# 8Enc.net
KiCad netlist of a schematic drawn in EAGLE
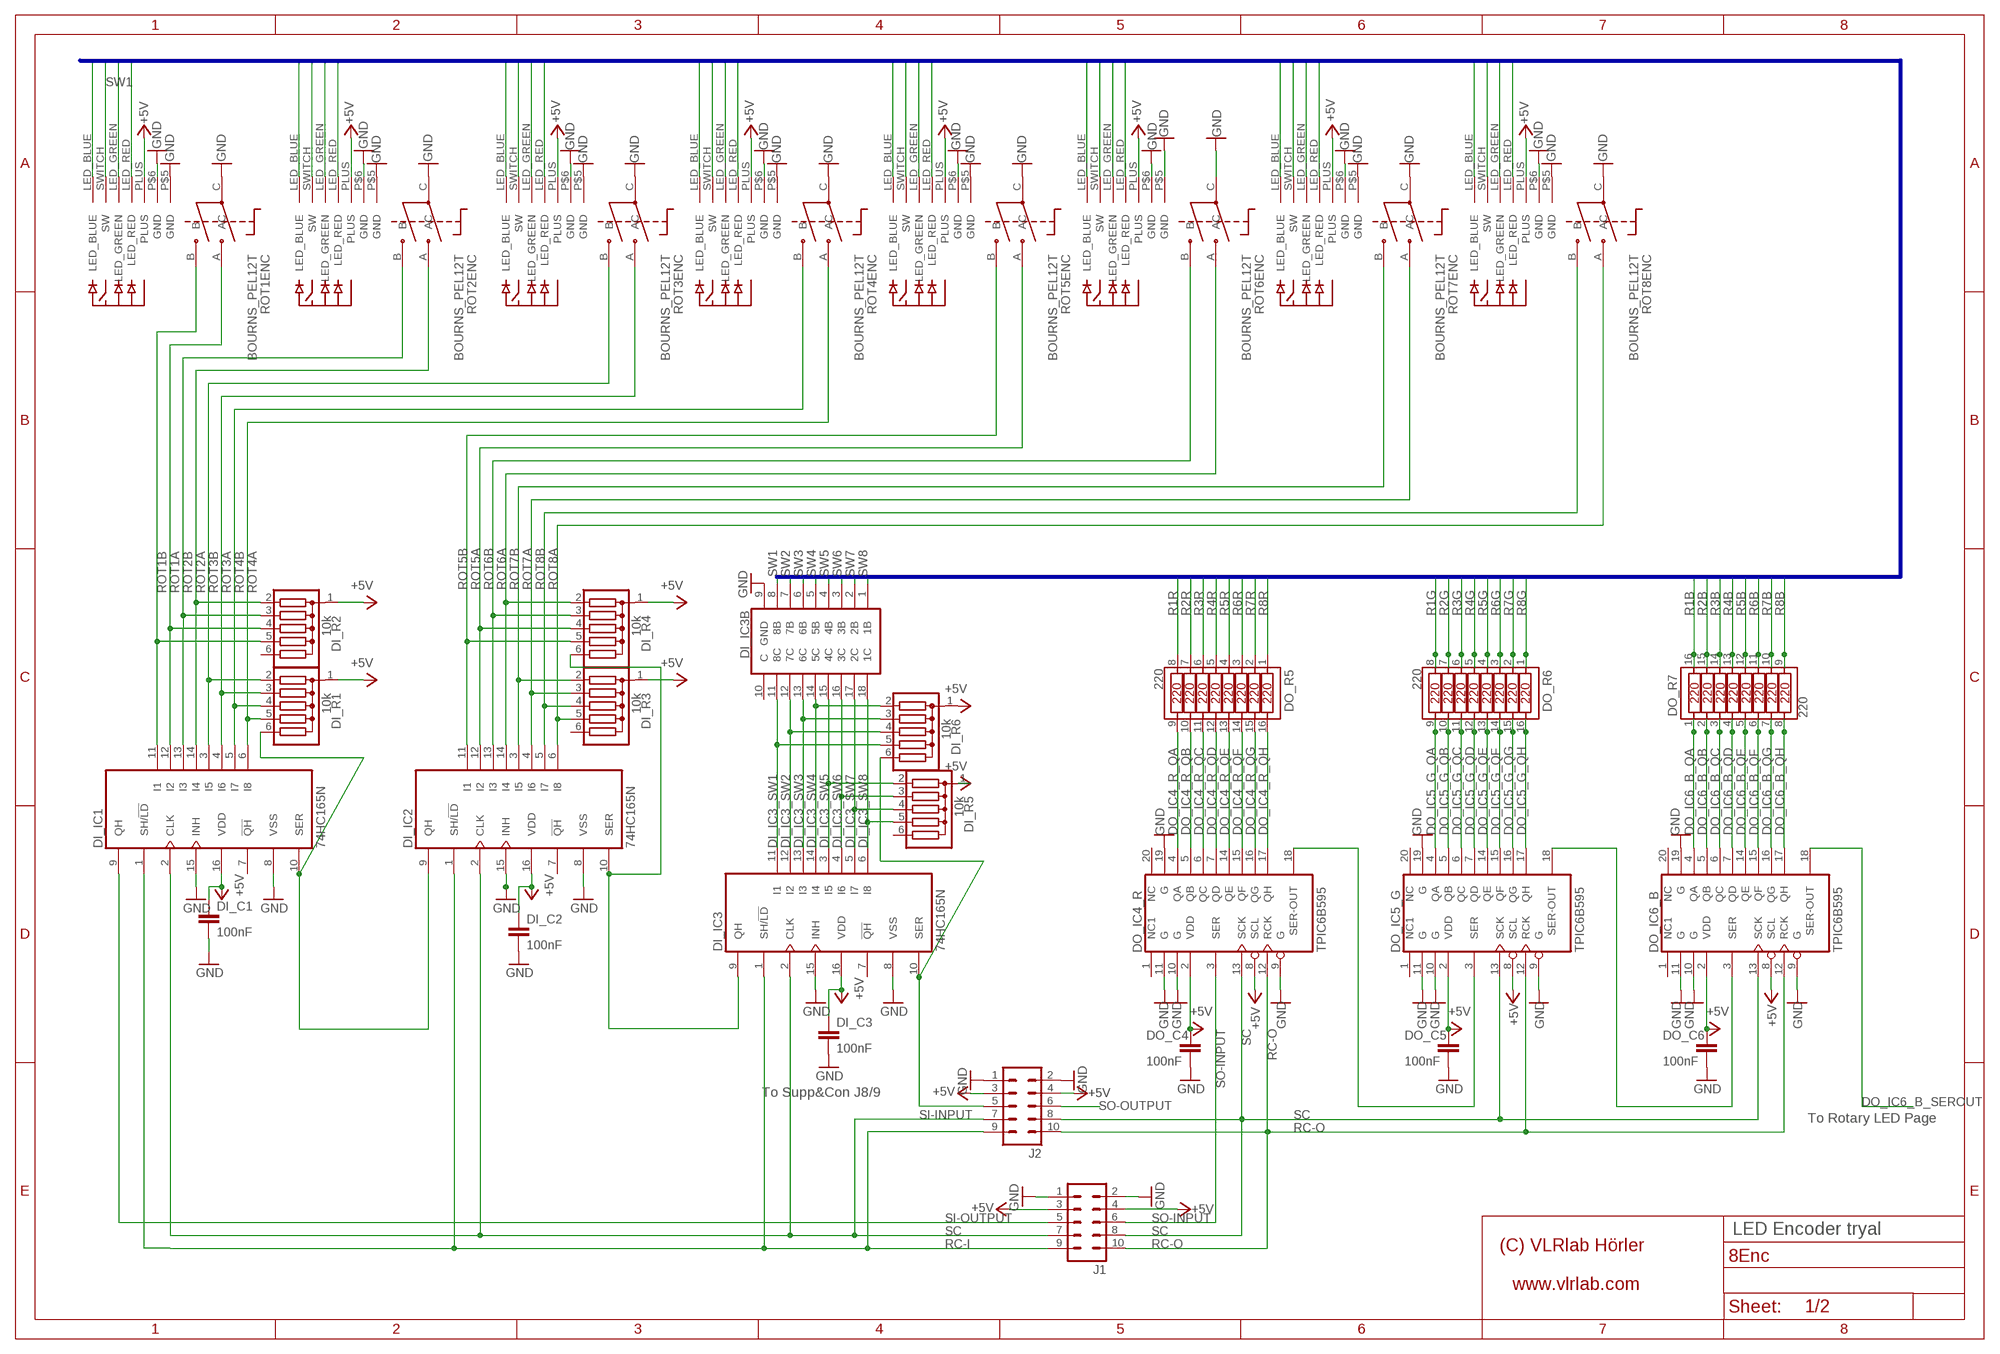
[diagram p0: schematic, sheet 1]
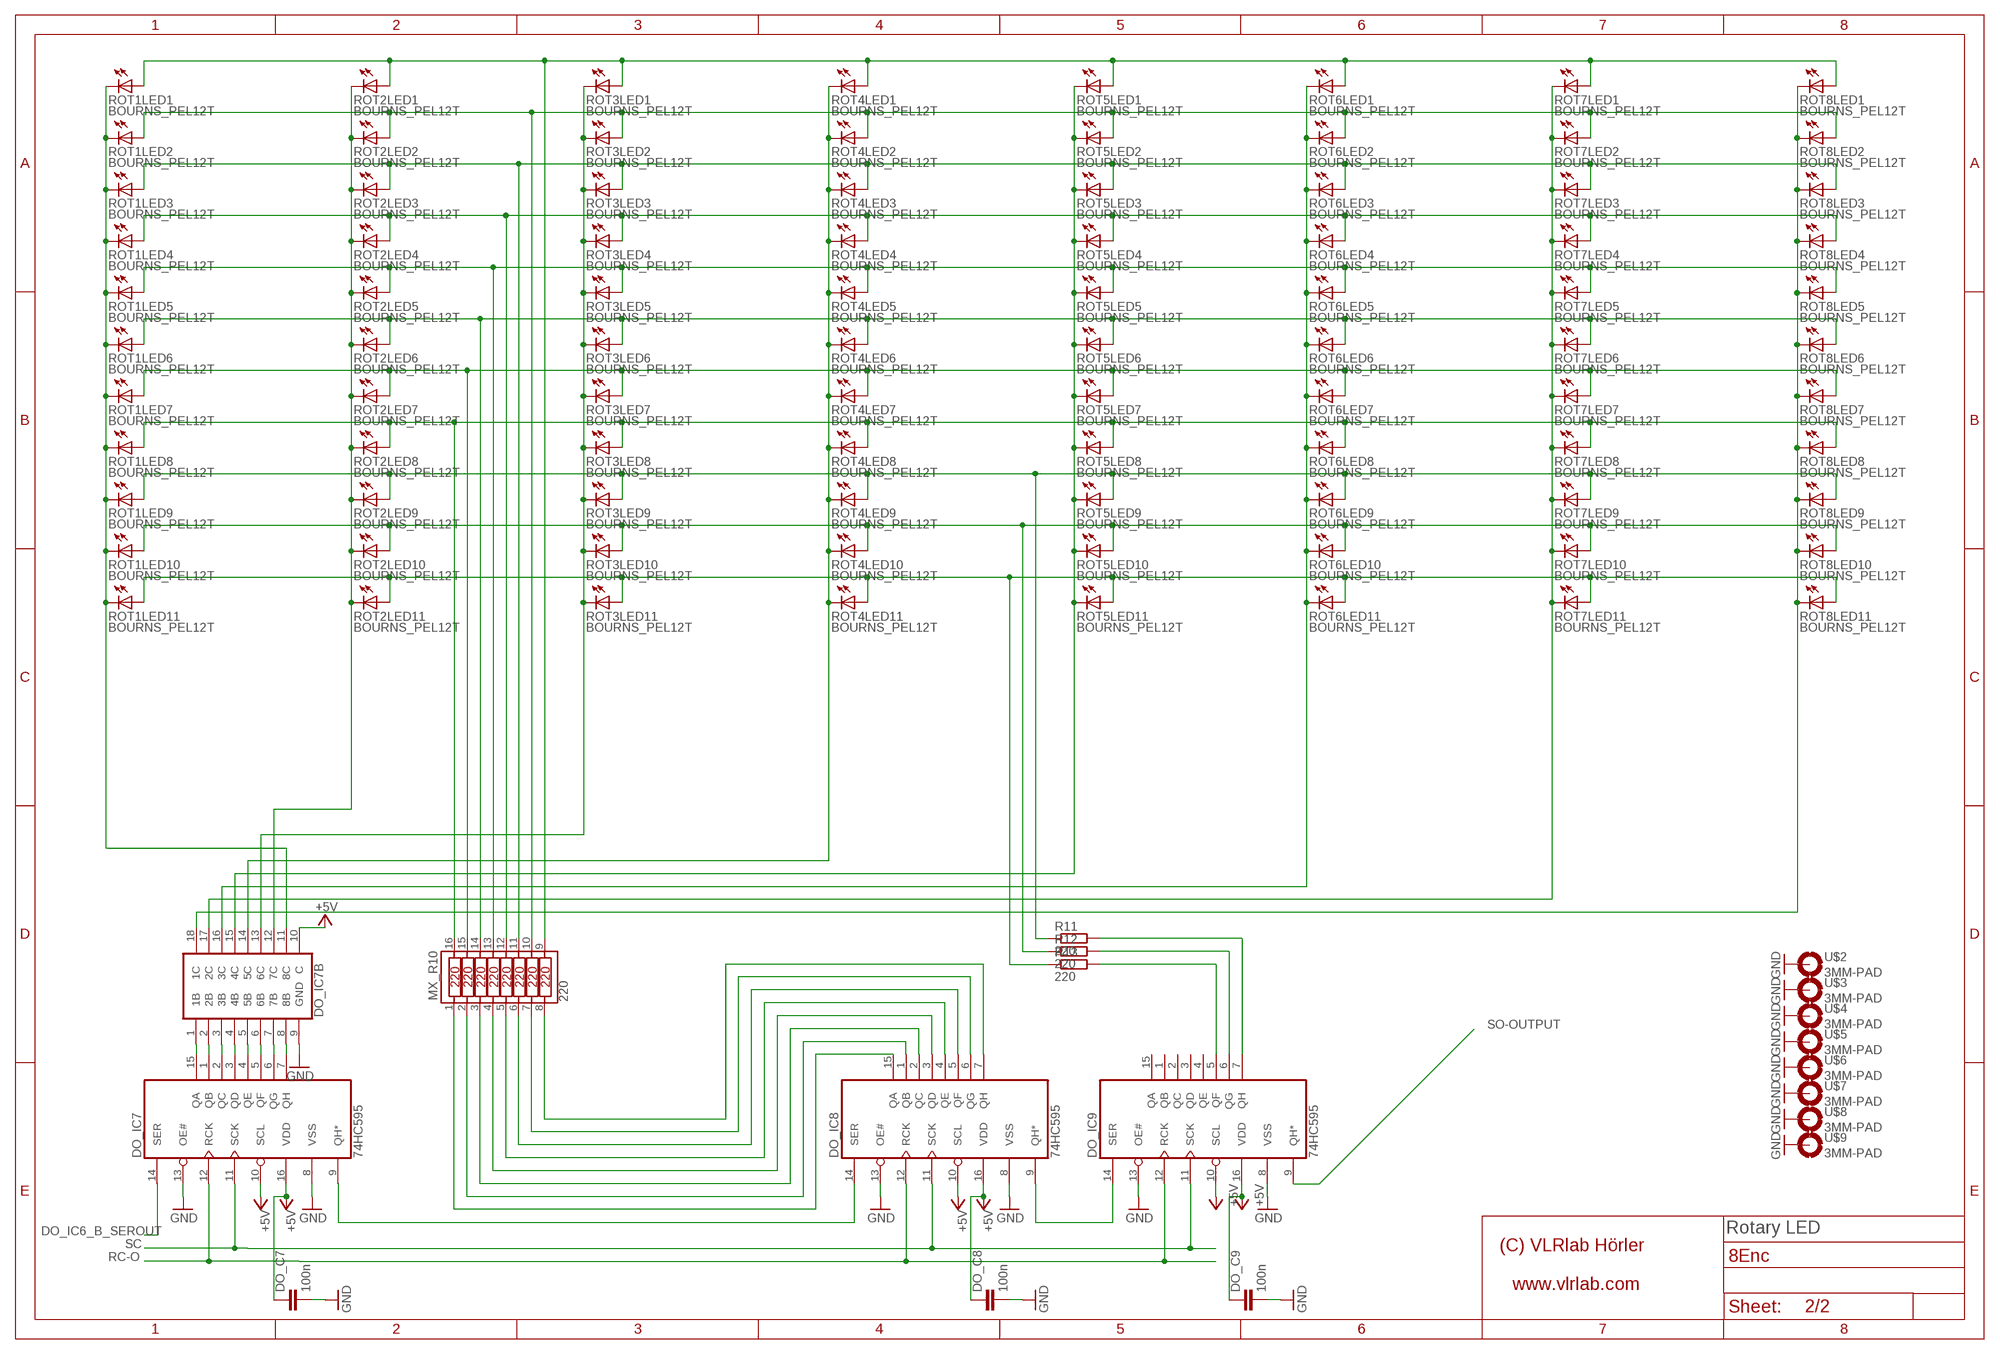
[diagram p1: schematic, sheet 2]

(export (version "E")
  (design (tool "Eeschema 10.0.6"))
  (components
    (comp (ref "DO_C7")
      (value "100n")
      (footprint "eagle-import:C025-024X044")
      (libsource (lib "eagle-import") (part "C-EU025-024X044"))
    )
    (comp (ref "DO_C8")
      (value "100n")
      (footprint "eagle-import:C025-024X044")
      (libsource (lib "eagle-import") (part "C-EU025-024X044"))
    )
    (comp (ref "DO_C9")
      (value "100n")
      (footprint "eagle-import:C025-024X044")
      (libsource (lib "eagle-import") (part "C-EU025-024X044"))
    )
    (comp (ref "DO_IC7")
      (value "74HC595")
      (footprint "eagle-import:SO16D")
      (libsource (lib "eagle-import") (part "595-541-165-uln2803_74HC595SO16D"))
    )
    (comp (ref "DO_IC7B")
      (value "ULN2803SO18W")
      (footprint "eagle-import:SO18W")
      (libsource (lib "eagle-import") (part "ULN2803SO18W"))
    )
    (comp (ref "DO_IC8")
      (value "74HC595")
      (footprint "eagle-import:SO16D")
      (libsource (lib "eagle-import") (part "595-541-165-uln2803_74HC595SO16D"))
    )
    (comp (ref "DO_IC9")
      (value "74HC595")
      (footprint "eagle-import:SO16D")
      (libsource (lib "eagle-import") (part "595-541-165-uln2803_74HC595SO16D"))
    )
    (comp (ref "MX_R10")
      (value "220")
      (footprint "eagle-import:SOIC16W")
      (libsource (lib "eagle-import") (part "4816P-1SOIC16W"))
    )
    (comp (ref "R11")
      (value "220")
      (footprint "eagle-import:0204_7")
      (libsource (lib "eagle-import") (part "R-EU_0204/7"))
    )
    (comp (ref "R12")
      (value "220")
      (footprint "eagle-import:0204_7")
      (libsource (lib "eagle-import") (part "R-EU_0204/7"))
    )
    (comp (ref "R13")
      (value "220")
      (footprint "eagle-import:0204_7")
      (libsource (lib "eagle-import") (part "R-EU_0204/7"))
    )
    (comp (ref "ROT1")
      (value "BOURNS_PEL12T")
      (footprint "eagle-import:PEL12T_11-LED-RING")
      (libsource (lib "eagle-import") (part "BOURNS_PEL12T_11-LED-RING"))
    )
    (comp (ref "ROT2")
      (value "BOURNS_PEL12T")
      (footprint "eagle-import:PEL12T_11-LED-RING")
      (libsource (lib "eagle-import") (part "BOURNS_PEL12T_11-LED-RING"))
    )
    (comp (ref "ROT3")
      (value "BOURNS_PEL12T")
      (footprint "eagle-import:PEL12T_11-LED-RING")
      (libsource (lib "eagle-import") (part "BOURNS_PEL12T_11-LED-RING"))
    )
    (comp (ref "ROT4")
      (value "BOURNS_PEL12T")
      (footprint "eagle-import:PEL12T_11-LED-RING")
      (libsource (lib "eagle-import") (part "BOURNS_PEL12T_11-LED-RING"))
    )
    (comp (ref "ROT5")
      (value "BOURNS_PEL12T")
      (footprint "eagle-import:PEL12T_11-LED-RING")
      (libsource (lib "eagle-import") (part "BOURNS_PEL12T_11-LED-RING"))
    )
    (comp (ref "ROT6")
      (value "BOURNS_PEL12T")
      (footprint "eagle-import:PEL12T_11-LED-RING")
      (libsource (lib "eagle-import") (part "BOURNS_PEL12T_11-LED-RING"))
    )
    (comp (ref "ROT7")
      (value "BOURNS_PEL12T")
      (footprint "eagle-import:PEL12T_11-LED-RING")
      (libsource (lib "eagle-import") (part "BOURNS_PEL12T_11-LED-RING"))
    )
    (comp (ref "ROT8")
      (value "BOURNS_PEL12T")
      (footprint "eagle-import:PEL12T_11-LED-RING")
      (libsource (lib "eagle-import") (part "BOURNS_PEL12T_11-LED-RING"))
    )
    (comp (ref "U$2")
      (value "3MM-PAD")
      (footprint "eagle-import:3MM-PAD")
      (libsource (lib "eagle-import") (part "3MM-PAD"))
    )
    (comp (ref "U$3")
      (value "3MM-PAD")
      (footprint "eagle-import:3MM-PAD")
      (libsource (lib "eagle-import") (part "3MM-PAD"))
    )
    (comp (ref "U$4")
      (value "3MM-PAD")
      (footprint "eagle-import:3MM-PAD")
      (libsource (lib "eagle-import") (part "3MM-PAD"))
    )
    (comp (ref "U$5")
      (value "3MM-PAD")
      (footprint "eagle-import:3MM-PAD")
      (libsource (lib "eagle-import") (part "3MM-PAD"))
    )
    (comp (ref "U$6")
      (value "3MM-PAD")
      (footprint "eagle-import:3MM-PAD")
      (libsource (lib "eagle-import") (part "3MM-PAD"))
    )
    (comp (ref "U$7")
      (value "3MM-PAD")
      (footprint "eagle-import:3MM-PAD")
      (libsource (lib "eagle-import") (part "3MM-PAD"))
    )
    (comp (ref "U$8")
      (value "3MM-PAD")
      (footprint "eagle-import:3MM-PAD")
      (libsource (lib "eagle-import") (part "3MM-PAD"))
    )
    (comp (ref "U$9")
      (value "3MM-PAD")
      (footprint "eagle-import:3MM-PAD")
      (libsource (lib "eagle-import") (part "3MM-PAD"))
    )
    (comp (ref "DI_C1")
      (value "100nF")
      (footprint "eagle-import:C025-024X044")
      (libsource (lib "eagle-import") (part "C-EU025-024X044"))
    )
    (comp (ref "DI_C2")
      (value "100nF")
      (footprint "eagle-import:C025-024X044")
      (libsource (lib "eagle-import") (part "C-EU025-024X044"))
    )
    (comp (ref "DI_C3")
      (value "100nF")
      (footprint "eagle-import:C025-024X044")
      (libsource (lib "eagle-import") (part "C-EU025-024X044"))
    )
    (comp (ref "DI_IC1")
      (value "74HC165N")
      (footprint "eagle-import:SO16D")
      (libsource (lib "eagle-import") (part "74HC165NSO16D"))
    )
    (comp (ref "DI_IC2")
      (value "74HC165N")
      (footprint "eagle-import:SO16D")
      (libsource (lib "eagle-import") (part "74HC165NSO16D"))
    )
    (comp (ref "DI_IC3")
      (value "74HC165N")
      (footprint "eagle-import:SO16D")
      (libsource (lib "eagle-import") (part "74HC165NSO16D"))
    )
    (comp (ref "DI_IC3B")
      (value "ULN2803SO18W")
      (footprint "eagle-import:SO18W")
      (libsource (lib "eagle-import") (part "ULN2803SO18W"))
    )
    (comp (ref "DI_R1")
      (value "10k")
      (footprint "eagle-import:SIL6")
      (libsource (lib "eagle-import") (part "4306R"))
    )
    (comp (ref "DI_R2")
      (value "10k")
      (footprint "eagle-import:SIL6")
      (libsource (lib "eagle-import") (part "4306R"))
    )
    (comp (ref "DI_R3")
      (value "10k")
      (footprint "eagle-import:SIL6")
      (libsource (lib "eagle-import") (part "4306R"))
    )
    (comp (ref "DI_R4")
      (value "10k")
      (footprint "eagle-import:SIL6")
      (libsource (lib "eagle-import") (part "4306R"))
    )
    (comp (ref "DI_R5")
      (value "10k")
      (footprint "eagle-import:SIL6")
      (libsource (lib "eagle-import") (part "4306R"))
    )
    (comp (ref "DI_R6")
      (value "10k")
      (footprint "eagle-import:SIL6")
      (libsource (lib "eagle-import") (part "4306R"))
    )
    (comp (ref "DO_C4")
      (value "100nF")
      (footprint "eagle-import:C025-024X044")
      (libsource (lib "eagle-import") (part "C-EU025-024X044"))
    )
    (comp (ref "DO_C5")
      (value "100nF")
      (footprint "eagle-import:C025-024X044")
      (libsource (lib "eagle-import") (part "C-EU025-024X044"))
    )
    (comp (ref "DO_C6")
      (value "100nF")
      (footprint "eagle-import:C025-024X044")
      (libsource (lib "eagle-import") (part "C-EU025-024X044"))
    )
    (comp (ref "DO_IC4_R")
      (value "TPIC6B595")
      (footprint "eagle-import:SO20W")
      (libsource (lib "eagle-import") (part "TPIC6B595SO20W"))
    )
    (comp (ref "DO_IC5_G")
      (value "TPIC6B595")
      (footprint "eagle-import:SO20W")
      (libsource (lib "eagle-import") (part "TPIC6B595SO20W"))
    )
    (comp (ref "DO_IC6_B")
      (value "TPIC6B595")
      (footprint "eagle-import:SO20W")
      (libsource (lib "eagle-import") (part "TPIC6B595SO20W"))
    )
    (comp (ref "DO_R5")
      (value "220")
      (footprint "eagle-import:SOIC16W")
      (libsource (lib "eagle-import") (part "4816P-1SOIC16W"))
    )
    (comp (ref "DO_R6")
      (value "220")
      (footprint "eagle-import:SOIC16W")
      (libsource (lib "eagle-import") (part "4816P-1SOIC16W"))
    )
    (comp (ref "DO_R7")
      (value "220")
      (footprint "eagle-import:SOIC16W")
      (libsource (lib "eagle-import") (part "4816P-1SOIC16W"))
    )
    (comp (ref "J1")
      (value "ML10")
      (footprint "eagle-import:ML10")
      (libsource (lib "eagle-import") (part "ML10"))
    )
    (comp (ref "J2")
      (value "ML10")
      (footprint "eagle-import:ML10")
      (libsource (lib "eagle-import") (part "ML10"))
    )
  )
  (nets
    (net (code "1") (name "+5V") (class "Default")
      (node (ref "DI_C1") (pin "1") (pinfunction "1_1") (pintype "passive"))
      (node (ref "DI_C2") (pin "1") (pinfunction "1_1") (pintype "passive"))
      (node (ref "DI_C3") (pin "1") (pinfunction "1_1") (pintype "passive"))
      (node (ref "DI_IC1") (pin "16") (pinfunction "VDD_16") (pintype "power_in"))
      (node (ref "DI_IC2") (pin "16") (pinfunction "VDD_16") (pintype "power_in"))
      (node (ref "DI_IC3") (pin "16") (pinfunction "VDD_16") (pintype "power_in"))
      (node (ref "DI_R1") (pin "1") (pinfunction "1_1") (pintype "passive"))
      (node (ref "DI_R2") (pin "1") (pinfunction "1_1") (pintype "passive"))
      (node (ref "DI_R3") (pin "1") (pinfunction "1_1") (pintype "passive"))
      (node (ref "DI_R4") (pin "1") (pinfunction "1_1") (pintype "passive"))
      (node (ref "DI_R5") (pin "1") (pinfunction "1_1") (pintype "passive"))
      (node (ref "DI_R6") (pin "1") (pinfunction "1_1") (pintype "passive"))
      (node (ref "DO_C4") (pin "1") (pinfunction "1_1") (pintype "passive"))
      (node (ref "DO_C5") (pin "1") (pinfunction "1_1") (pintype "passive"))
      (node (ref "DO_C6") (pin "1") (pinfunction "1_1") (pintype "passive"))
      (node (ref "DO_C7") (pin "1") (pinfunction "1_1") (pintype "passive"))
      (node (ref "DO_C8") (pin "1") (pinfunction "1_1") (pintype "passive"))
      (node (ref "DO_C9") (pin "1") (pinfunction "1_1") (pintype "passive"))
      (node (ref "DO_IC4_R") (pin "2") (pinfunction "VDD_2") (pintype "power_in"))
      (node (ref "DO_IC4_R") (pin "8") (pinfunction "SCL_8") (pintype "input"))
      (node (ref "DO_IC5_G") (pin "2") (pinfunction "VDD_2") (pintype "power_in"))
      (node (ref "DO_IC5_G") (pin "8") (pinfunction "SCL_8") (pintype "input"))
      (node (ref "DO_IC6_B") (pin "2") (pinfunction "VDD_2") (pintype "power_in"))
      (node (ref "DO_IC6_B") (pin "8") (pinfunction "SCL_8") (pintype "input"))
      (node (ref "DO_IC7") (pin "10") (pinfunction "SCL_10") (pintype "input"))
      (node (ref "DO_IC7") (pin "16") (pinfunction "VDD_16") (pintype "power_in"))
      (node (ref "DO_IC7B") (pin "10") (pinfunction "C_10") (pintype "passive"))
      (node (ref "DO_IC8") (pin "10") (pinfunction "SCL_10") (pintype "input"))
      (node (ref "DO_IC8") (pin "16") (pinfunction "VDD_16") (pintype "power_in"))
      (node (ref "DO_IC9") (pin "10") (pinfunction "SCL_10") (pintype "input"))
      (node (ref "DO_IC9") (pin "16") (pinfunction "VDD_16") (pintype "power_in"))
      (node (ref "J1") (pin "3") (pinfunction "3_3") (pintype "passive"))
      (node (ref "J1") (pin "4") (pinfunction "4_4") (pintype "passive"))
      (node (ref "J2") (pin "3") (pinfunction "3_3") (pintype "passive"))
      (node (ref "J2") (pin "4") (pinfunction "4_4") (pintype "passive"))
      (node (ref "ROT1") (pin "PLUS") (pinfunction "PLUS_PLUS") (pintype "bidirectional"))
      (node (ref "ROT2") (pin "PLUS") (pinfunction "PLUS_PLUS") (pintype "bidirectional"))
      (node (ref "ROT3") (pin "PLUS") (pinfunction "PLUS_PLUS") (pintype "bidirectional"))
      (node (ref "ROT4") (pin "PLUS") (pinfunction "PLUS_PLUS") (pintype "bidirectional"))
      (node (ref "ROT5") (pin "PLUS") (pinfunction "PLUS_PLUS") (pintype "bidirectional"))
      (node (ref "ROT6") (pin "PLUS") (pinfunction "PLUS_PLUS") (pintype "bidirectional"))
      (node (ref "ROT7") (pin "PLUS") (pinfunction "PLUS_PLUS") (pintype "bidirectional"))
      (node (ref "ROT8") (pin "PLUS") (pinfunction "PLUS_PLUS") (pintype "bidirectional"))
    )
    (net (code "2") (name "DI_IC3_SW1") (class "Default")
      (node (ref "DI_IC3") (pin "11") (pinfunction "I1_11") (pintype "input"))
      (node (ref "DI_IC3B") (pin "11") (pinfunction "8C_11") (pintype "open_collector"))
      (node (ref "DI_R6") (pin "5") (pinfunction "5_5") (pintype "passive"))
    )
    (net (code "3") (name "DI_IC3_SW2") (class "Default")
      (node (ref "DI_IC3") (pin "12") (pinfunction "I2_12") (pintype "input"))
      (node (ref "DI_IC3B") (pin "12") (pinfunction "7C_12") (pintype "open_collector"))
      (node (ref "DI_R6") (pin "4") (pinfunction "4_4") (pintype "passive"))
    )
    (net (code "4") (name "DI_IC3_SW3") (class "Default")
      (node (ref "DI_IC3") (pin "13") (pinfunction "I3_13") (pintype "input"))
      (node (ref "DI_IC3B") (pin "13") (pinfunction "6C_13") (pintype "open_collector"))
      (node (ref "DI_R6") (pin "3") (pinfunction "3_3") (pintype "passive"))
    )
    (net (code "5") (name "DI_IC3_SW4") (class "Default")
      (node (ref "DI_IC3") (pin "14") (pinfunction "I4_14") (pintype "input"))
      (node (ref "DI_IC3B") (pin "14") (pinfunction "5C_14") (pintype "open_collector"))
      (node (ref "DI_R6") (pin "2") (pinfunction "2_2") (pintype "passive"))
    )
    (net (code "6") (name "DI_IC3_SW5") (class "Default")
      (node (ref "DI_IC3") (pin "3") (pinfunction "I5_3") (pintype "input"))
      (node (ref "DI_IC3B") (pin "15") (pinfunction "4C_15") (pintype "open_collector"))
      (node (ref "DI_R5") (pin "2") (pinfunction "2_2") (pintype "passive"))
    )
    (net (code "7") (name "DI_IC3_SW6") (class "Default")
      (node (ref "DI_IC3") (pin "4") (pinfunction "I6_4") (pintype "input"))
      (node (ref "DI_IC3B") (pin "16") (pinfunction "3C_16") (pintype "open_collector"))
      (node (ref "DI_R5") (pin "3") (pinfunction "3_3") (pintype "passive"))
    )
    (net (code "8") (name "DI_IC3_SW7") (class "Default")
      (node (ref "DI_IC3") (pin "5") (pinfunction "I7_5") (pintype "input"))
      (node (ref "DI_IC3B") (pin "17") (pinfunction "2C_17") (pintype "open_collector"))
      (node (ref "DI_R5") (pin "4") (pinfunction "4_4") (pintype "passive"))
    )
    (net (code "9") (name "DI_IC3_SW8") (class "Default")
      (node (ref "DI_IC3") (pin "6") (pinfunction "I8_6") (pintype "input"))
      (node (ref "DI_IC3B") (pin "18") (pinfunction "1C_18") (pintype "open_collector"))
      (node (ref "DI_R5") (pin "5") (pinfunction "5_5") (pintype "passive"))
    )
    (net (code "10") (name "DO_IC4_R_QA") (class "Default")
      (node (ref "DO_IC4_R") (pin "4") (pinfunction "QA_4") (pintype "tri_state"))
      (node (ref "DO_R5") (pin "9") (pinfunction "P$9_9") (pintype "passive"))
    )
    (net (code "11") (name "DO_IC4_R_QB") (class "Default")
      (node (ref "DO_IC4_R") (pin "5") (pinfunction "QB_5") (pintype "tri_state"))
      (node (ref "DO_R5") (pin "10") (pinfunction "P$10_10") (pintype "passive"))
    )
    (net (code "12") (name "DO_IC4_R_QC") (class "Default")
      (node (ref "DO_IC4_R") (pin "6") (pinfunction "QC_6") (pintype "tri_state"))
      (node (ref "DO_R5") (pin "11") (pinfunction "P$11_11") (pintype "passive"))
    )
    (net (code "13") (name "DO_IC4_R_QD") (class "Default")
      (node (ref "DO_IC4_R") (pin "7") (pinfunction "QD_7") (pintype "tri_state"))
      (node (ref "DO_R5") (pin "12") (pinfunction "P$12_12") (pintype "passive"))
    )
    (net (code "14") (name "DO_IC4_R_QE") (class "Default")
      (node (ref "DO_IC4_R") (pin "14") (pinfunction "QE_14") (pintype "tri_state"))
      (node (ref "DO_R5") (pin "13") (pinfunction "P$13_13") (pintype "passive"))
    )
    (net (code "15") (name "DO_IC4_R_QF") (class "Default")
      (node (ref "DO_IC4_R") (pin "15") (pinfunction "QF_15") (pintype "tri_state"))
      (node (ref "DO_R5") (pin "14") (pinfunction "P$14_14") (pintype "passive"))
    )
    (net (code "16") (name "DO_IC4_R_QG") (class "Default")
      (node (ref "DO_IC4_R") (pin "16") (pinfunction "QG_16") (pintype "tri_state"))
      (node (ref "DO_R5") (pin "15") (pinfunction "P$15_15") (pintype "passive"))
    )
    (net (code "17") (name "DO_IC4_R_QH") (class "Default")
      (node (ref "DO_IC4_R") (pin "17") (pinfunction "QH_17") (pintype "tri_state"))
      (node (ref "DO_R5") (pin "16") (pinfunction "P$16_16") (pintype "passive"))
    )
    (net (code "18") (name "DO_IC5_G_QA") (class "Default")
      (node (ref "DO_IC5_G") (pin "4") (pinfunction "QA_4") (pintype "tri_state"))
      (node (ref "DO_R6") (pin "9") (pinfunction "P$9_9") (pintype "passive"))
    )
    (net (code "19") (name "DO_IC5_G_QB") (class "Default")
      (node (ref "DO_IC5_G") (pin "5") (pinfunction "QB_5") (pintype "tri_state"))
      (node (ref "DO_R6") (pin "10") (pinfunction "P$10_10") (pintype "passive"))
    )
    (net (code "20") (name "DO_IC5_G_QC") (class "Default")
      (node (ref "DO_IC5_G") (pin "6") (pinfunction "QC_6") (pintype "tri_state"))
      (node (ref "DO_R6") (pin "11") (pinfunction "P$11_11") (pintype "passive"))
    )
    (net (code "21") (name "DO_IC5_G_QD") (class "Default")
      (node (ref "DO_IC5_G") (pin "7") (pinfunction "QD_7") (pintype "tri_state"))
      (node (ref "DO_R6") (pin "12") (pinfunction "P$12_12") (pintype "passive"))
    )
    (net (code "22") (name "DO_IC5_G_QE") (class "Default")
      (node (ref "DO_IC5_G") (pin "14") (pinfunction "QE_14") (pintype "tri_state"))
      (node (ref "DO_R6") (pin "13") (pinfunction "P$13_13") (pintype "passive"))
    )
    (net (code "23") (name "DO_IC5_G_QF") (class "Default")
      (node (ref "DO_IC5_G") (pin "15") (pinfunction "QF_15") (pintype "tri_state"))
      (node (ref "DO_R6") (pin "14") (pinfunction "P$14_14") (pintype "passive"))
    )
    (net (code "24") (name "DO_IC5_G_QG") (class "Default")
      (node (ref "DO_IC5_G") (pin "16") (pinfunction "QG_16") (pintype "tri_state"))
      (node (ref "DO_R6") (pin "15") (pinfunction "P$15_15") (pintype "passive"))
    )
    (net (code "25") (name "DO_IC5_G_QH") (class "Default")
      (node (ref "DO_IC5_G") (pin "17") (pinfunction "QH_17") (pintype "tri_state"))
      (node (ref "DO_R6") (pin "16") (pinfunction "P$16_16") (pintype "passive"))
    )
    (net (code "26") (name "DO_IC6_B_QA") (class "Default")
      (node (ref "DO_IC6_B") (pin "4") (pinfunction "QA_4") (pintype "tri_state"))
      (node (ref "DO_R7") (pin "1") (pinfunction "P$1_1") (pintype "passive"))
    )
    (net (code "27") (name "DO_IC6_B_QB") (class "Default")
      (node (ref "DO_IC6_B") (pin "5") (pinfunction "QB_5") (pintype "tri_state"))
      (node (ref "DO_R7") (pin "2") (pinfunction "P$2_2") (pintype "passive"))
    )
    (net (code "28") (name "DO_IC6_B_QC") (class "Default")
      (node (ref "DO_IC6_B") (pin "6") (pinfunction "QC_6") (pintype "tri_state"))
      (node (ref "DO_R7") (pin "3") (pinfunction "P$3_3") (pintype "passive"))
    )
    (net (code "29") (name "DO_IC6_B_QD") (class "Default")
      (node (ref "DO_IC6_B") (pin "7") (pinfunction "QD_7") (pintype "tri_state"))
      (node (ref "DO_R7") (pin "4") (pinfunction "P$4_4") (pintype "passive"))
    )
    (net (code "30") (name "DO_IC6_B_QE") (class "Default")
      (node (ref "DO_IC6_B") (pin "14") (pinfunction "QE_14") (pintype "tri_state"))
      (node (ref "DO_R7") (pin "5") (pinfunction "P$5_5") (pintype "passive"))
    )
    (net (code "31") (name "DO_IC6_B_QF") (class "Default")
      (node (ref "DO_IC6_B") (pin "15") (pinfunction "QF_15") (pintype "tri_state"))
      (node (ref "DO_R7") (pin "6") (pinfunction "P$6_6") (pintype "passive"))
    )
    (net (code "32") (name "DO_IC6_B_QG") (class "Default")
      (node (ref "DO_IC6_B") (pin "16") (pinfunction "QG_16") (pintype "tri_state"))
      (node (ref "DO_R7") (pin "7") (pinfunction "P$7_7") (pintype "passive"))
    )
    (net (code "33") (name "DO_IC6_B_QH") (class "Default")
      (node (ref "DO_IC6_B") (pin "17") (pinfunction "QH_17") (pintype "tri_state"))
      (node (ref "DO_R7") (pin "8") (pinfunction "P$8_8") (pintype "passive"))
    )
    (net (code "34") (name "DO_IC6_B_SEROUT") (class "Default")
      (node (ref "DO_IC6_B") (pin "18") (pinfunction "SER-OUT_18") (pintype "tri_state"))
      (node (ref "DO_IC7") (pin "14") (pinfunction "SER_14") (pintype "input"))
    )
    (net (code "35") (name "GND") (class "Default")
      (node (ref "DI_C1") (pin "2") (pinfunction "2_2") (pintype "passive"))
      (node (ref "DI_C2") (pin "2") (pinfunction "2_2") (pintype "passive"))
      (node (ref "DI_C3") (pin "2") (pinfunction "2_2") (pintype "passive"))
      (node (ref "DI_IC1") (pin "15") (pinfunction "INH_15") (pintype "input"))
      (node (ref "DI_IC1") (pin "8") (pinfunction "VSS_8") (pintype "power_in"))
      (node (ref "DI_IC2") (pin "15") (pinfunction "INH_15") (pintype "input"))
      (node (ref "DI_IC2") (pin "8") (pinfunction "VSS_8") (pintype "power_in"))
      (node (ref "DI_IC3") (pin "15") (pinfunction "INH_15") (pintype "input"))
      (node (ref "DI_IC3") (pin "8") (pinfunction "VSS_8") (pintype "power_in"))
      (node (ref "DI_IC3B") (pin "9") (pinfunction "GND_9") (pintype "power_in"))
      (node (ref "DO_C4") (pin "2") (pinfunction "2_2") (pintype "passive"))
      (node (ref "DO_C5") (pin "2") (pinfunction "2_2") (pintype "passive"))
      (node (ref "DO_C6") (pin "2") (pinfunction "2_2") (pintype "passive"))
      (node (ref "DO_C7") (pin "2") (pinfunction "2_2") (pintype "passive"))
      (node (ref "DO_C8") (pin "2") (pinfunction "2_2") (pintype "passive"))
      (node (ref "DO_C9") (pin "2") (pinfunction "2_2") (pintype "passive"))
      (node (ref "DO_IC4_R") (pin "10") (pinfunction "G_10") (pintype "power_in"))
      (node (ref "DO_IC4_R") (pin "11") (pinfunction "G_11") (pintype "power_in"))
      (node (ref "DO_IC4_R") (pin "19") (pinfunction "G_19") (pintype "tri_state"))
      (node (ref "DO_IC4_R") (pin "9") (pinfunction "G_9") (pintype "input"))
      (node (ref "DO_IC5_G") (pin "10") (pinfunction "G_10") (pintype "power_in"))
      (node (ref "DO_IC5_G") (pin "11") (pinfunction "G_11") (pintype "power_in"))
      (node (ref "DO_IC5_G") (pin "19") (pinfunction "G_19") (pintype "tri_state"))
      (node (ref "DO_IC5_G") (pin "9") (pinfunction "G_9") (pintype "input"))
      (node (ref "DO_IC6_B") (pin "10") (pinfunction "G_10") (pintype "power_in"))
      (node (ref "DO_IC6_B") (pin "11") (pinfunction "G_11") (pintype "power_in"))
      (node (ref "DO_IC6_B") (pin "19") (pinfunction "G_19") (pintype "tri_state"))
      (node (ref "DO_IC6_B") (pin "9") (pinfunction "G_9") (pintype "input"))
      (node (ref "DO_IC7") (pin "13") (pinfunction "OE#_13") (pintype "input"))
      (node (ref "DO_IC7") (pin "8") (pinfunction "VSS_8") (pintype "power_in"))
      (node (ref "DO_IC7B") (pin "9") (pinfunction "GND_9") (pintype "power_in"))
      (node (ref "DO_IC8") (pin "13") (pinfunction "OE#_13") (pintype "input"))
      (node (ref "DO_IC8") (pin "8") (pinfunction "VSS_8") (pintype "power_in"))
      (node (ref "DO_IC9") (pin "13") (pinfunction "OE#_13") (pintype "input"))
      (node (ref "DO_IC9") (pin "8") (pinfunction "VSS_8") (pintype "power_in"))
      (node (ref "J1") (pin "1") (pinfunction "1_1") (pintype "passive"))
      (node (ref "J1") (pin "2") (pinfunction "2_2") (pintype "passive"))
      (node (ref "J2") (pin "1") (pinfunction "1_1") (pintype "passive"))
      (node (ref "J2") (pin "2") (pinfunction "2_2") (pintype "passive"))
      (node (ref "ROT1") (pin "C") (pinfunction "C_C") (pintype "bidirectional"))
      (node (ref "ROT1") (pin "P$5") (pinfunction "GND_P$5") (pintype "bidirectional"))
      (node (ref "ROT1") (pin "P$6") (pinfunction "GND_P$6") (pintype "bidirectional"))
      (node (ref "ROT2") (pin "C") (pinfunction "C_C") (pintype "bidirectional"))
      (node (ref "ROT2") (pin "P$5") (pinfunction "GND_P$5") (pintype "bidirectional"))
      (node (ref "ROT2") (pin "P$6") (pinfunction "GND_P$6") (pintype "bidirectional"))
      (node (ref "ROT3") (pin "C") (pinfunction "C_C") (pintype "bidirectional"))
      (node (ref "ROT3") (pin "P$5") (pinfunction "GND_P$5") (pintype "bidirectional"))
      (node (ref "ROT3") (pin "P$6") (pinfunction "GND_P$6") (pintype "bidirectional"))
      (node (ref "ROT4") (pin "C") (pinfunction "C_C") (pintype "bidirectional"))
      (node (ref "ROT4") (pin "P$5") (pinfunction "GND_P$5") (pintype "bidirectional"))
      (node (ref "ROT4") (pin "P$6") (pinfunction "GND_P$6") (pintype "bidirectional"))
      (node (ref "ROT5") (pin "C") (pinfunction "C_C") (pintype "bidirectional"))
      (node (ref "ROT5") (pin "P$5") (pinfunction "GND_P$5") (pintype "bidirectional"))
      (node (ref "ROT5") (pin "P$6") (pinfunction "GND_P$6") (pintype "bidirectional"))
      (node (ref "ROT6") (pin "C") (pinfunction "C_C") (pintype "bidirectional"))
      (node (ref "ROT6") (pin "P$5") (pinfunction "GND_P$5") (pintype "bidirectional"))
      (node (ref "ROT6") (pin "P$6") (pinfunction "GND_P$6") (pintype "bidirectional"))
      (node (ref "ROT7") (pin "C") (pinfunction "C_C") (pintype "bidirectional"))
      (node (ref "ROT7") (pin "P$5") (pinfunction "GND_P$5") (pintype "bidirectional"))
      (node (ref "ROT7") (pin "P$6") (pinfunction "GND_P$6") (pintype "bidirectional"))
      (node (ref "ROT8") (pin "C") (pinfunction "C_C") (pintype "bidirectional"))
      (node (ref "ROT8") (pin "P$5") (pinfunction "GND_P$5") (pintype "bidirectional"))
      (node (ref "ROT8") (pin "P$6") (pinfunction "GND_P$6") (pintype "bidirectional"))
      (node (ref "U$2") (pin "B3") (pinfunction "MOUNT_B3") (pintype "passive"))
      (node (ref "U$3") (pin "B3") (pinfunction "MOUNT_B3") (pintype "passive"))
      (node (ref "U$4") (pin "B3") (pinfunction "MOUNT_B3") (pintype "passive"))
      (node (ref "U$5") (pin "B3") (pinfunction "MOUNT_B3") (pintype "passive"))
      (node (ref "U$6") (pin "B3") (pinfunction "MOUNT_B3") (pintype "passive"))
      (node (ref "U$7") (pin "B3") (pinfunction "MOUNT_B3") (pintype "passive"))
      (node (ref "U$8") (pin "B3") (pinfunction "MOUNT_B3") (pintype "passive"))
      (node (ref "U$9") (pin "B3") (pinfunction "MOUNT_B3") (pintype "passive"))
    )
    (net (code "36") (name "Net-(DI_IC1-SER)") (class "Default")
      (node (ref "DI_IC1") (pin "10") (pinfunction "SER_10") (pintype "input"))
      (node (ref "DI_IC2") (pin "9") (pinfunction "QH_9") (pintype "output"))
      (node (ref "DI_R1") (pin "6") (pinfunction "6_6") (pintype "passive"))
    )
    (net (code "37") (name "Net-(DI_IC2-SER)") (class "Default")
      (node (ref "DI_IC2") (pin "10") (pinfunction "SER_10") (pintype "input"))
      (node (ref "DI_IC3") (pin "9") (pinfunction "QH_9") (pintype "output"))
      (node (ref "DI_R4") (pin "6") (pinfunction "6_6") (pintype "passive"))
    )
    (net (code "38") (name "Net-(DO_IC4_R-SER-OUT)") (class "Default")
      (node (ref "DO_IC4_R") (pin "18") (pinfunction "SER-OUT_18") (pintype "tri_state"))
      (node (ref "DO_IC5_G") (pin "3") (pinfunction "SER_3") (pintype "input"))
    )
    (net (code "39") (name "Net-(DO_IC5_G-SER-OUT)") (class "Default")
      (node (ref "DO_IC5_G") (pin "18") (pinfunction "SER-OUT_18") (pintype "tri_state"))
      (node (ref "DO_IC6_B") (pin "3") (pinfunction "SER_3") (pintype "input"))
    )
    (net (code "40") (name "Net-(DO_IC7-QA)") (class "Default")
      (node (ref "DO_IC7") (pin "15") (pinfunction "QA_15") (pintype "tri_state"))
      (node (ref "DO_IC7B") (pin "1") (pinfunction "1B_1") (pintype "input"))
    )
    (net (code "41") (name "Net-(DO_IC7-QB)") (class "Default")
      (node (ref "DO_IC7") (pin "1") (pinfunction "QB_1") (pintype "tri_state"))
      (node (ref "DO_IC7B") (pin "2") (pinfunction "2B_2") (pintype "input"))
    )
    (net (code "42") (name "Net-(DO_IC7-QC)") (class "Default")
      (node (ref "DO_IC7") (pin "2") (pinfunction "QC_2") (pintype "tri_state"))
      (node (ref "DO_IC7B") (pin "3") (pinfunction "3B_3") (pintype "input"))
    )
    (net (code "43") (name "Net-(DO_IC7-QD)") (class "Default")
      (node (ref "DO_IC7") (pin "3") (pinfunction "QD_3") (pintype "tri_state"))
      (node (ref "DO_IC7B") (pin "4") (pinfunction "4B_4") (pintype "input"))
    )
    (net (code "44") (name "Net-(DO_IC7-QE)") (class "Default")
      (node (ref "DO_IC7") (pin "4") (pinfunction "QE_4") (pintype "tri_state"))
      (node (ref "DO_IC7B") (pin "5") (pinfunction "5B_5") (pintype "input"))
    )
    (net (code "45") (name "Net-(DO_IC7-QF)") (class "Default")
      (node (ref "DO_IC7") (pin "5") (pinfunction "QF_5") (pintype "tri_state"))
      (node (ref "DO_IC7B") (pin "6") (pinfunction "6B_6") (pintype "input"))
    )
    (net (code "46") (name "Net-(DO_IC7-QG)") (class "Default")
      (node (ref "DO_IC7") (pin "6") (pinfunction "QG_6") (pintype "tri_state"))
      (node (ref "DO_IC7B") (pin "7") (pinfunction "7B_7") (pintype "input"))
    )
    (net (code "47") (name "Net-(DO_IC7-QH)") (class "Default")
      (node (ref "DO_IC7") (pin "7") (pinfunction "QH_7") (pintype "tri_state"))
      (node (ref "DO_IC7B") (pin "8") (pinfunction "8B_8") (pintype "input"))
    )
    (net (code "48") (name "Net-(DO_IC7-QH*)") (class "Default")
      (node (ref "DO_IC7") (pin "9") (pinfunction "QH*_9") (pintype "tri_state"))
      (node (ref "DO_IC8") (pin "14") (pinfunction "SER_14") (pintype "input"))
    )
    (net (code "49") (name "Net-(DO_IC7B-1C)") (class "Default")
      (node (ref "DO_IC7B") (pin "18") (pinfunction "1C_18") (pintype "open_collector"))
      (node (ref "ROT8") (pin "K1") (pinfunction "C_K1") (pintype "passive"))
      (node (ref "ROT8") (pin "K10") (pinfunction "C_K10") (pintype "passive"))
      (node (ref "ROT8") (pin "K12") (pinfunction "C_K12") (pintype "passive"))
      (node (ref "ROT8") (pin "K2") (pinfunction "C_K2") (pintype "passive"))
      (node (ref "ROT8") (pin "K3") (pinfunction "C_K3") (pintype "passive"))
      (node (ref "ROT8") (pin "K4") (pinfunction "C_K4") (pintype "passive"))
      (node (ref "ROT8") (pin "K5") (pinfunction "C_K5") (pintype "passive"))
      (node (ref "ROT8") (pin "K6") (pinfunction "C_K6") (pintype "passive"))
      (node (ref "ROT8") (pin "K7") (pinfunction "C_K7") (pintype "passive"))
      (node (ref "ROT8") (pin "K8") (pinfunction "C_K8") (pintype "passive"))
      (node (ref "ROT8") (pin "K9") (pinfunction "C_K9") (pintype "passive"))
    )
    (net (code "50") (name "Net-(DO_IC7B-2C)") (class "Default")
      (node (ref "DO_IC7B") (pin "17") (pinfunction "2C_17") (pintype "open_collector"))
      (node (ref "ROT7") (pin "K1") (pinfunction "C_K1") (pintype "passive"))
      (node (ref "ROT7") (pin "K10") (pinfunction "C_K10") (pintype "passive"))
      (node (ref "ROT7") (pin "K12") (pinfunction "C_K12") (pintype "passive"))
      (node (ref "ROT7") (pin "K2") (pinfunction "C_K2") (pintype "passive"))
      (node (ref "ROT7") (pin "K3") (pinfunction "C_K3") (pintype "passive"))
      (node (ref "ROT7") (pin "K4") (pinfunction "C_K4") (pintype "passive"))
      (node (ref "ROT7") (pin "K5") (pinfunction "C_K5") (pintype "passive"))
      (node (ref "ROT7") (pin "K6") (pinfunction "C_K6") (pintype "passive"))
      (node (ref "ROT7") (pin "K7") (pinfunction "C_K7") (pintype "passive"))
      (node (ref "ROT7") (pin "K8") (pinfunction "C_K8") (pintype "passive"))
      (node (ref "ROT7") (pin "K9") (pinfunction "C_K9") (pintype "passive"))
    )
    (net (code "51") (name "Net-(DO_IC7B-3C)") (class "Default")
      (node (ref "DO_IC7B") (pin "16") (pinfunction "3C_16") (pintype "open_collector"))
      (node (ref "ROT6") (pin "K1") (pinfunction "C_K1") (pintype "passive"))
      (node (ref "ROT6") (pin "K10") (pinfunction "C_K10") (pintype "passive"))
      (node (ref "ROT6") (pin "K12") (pinfunction "C_K12") (pintype "passive"))
      (node (ref "ROT6") (pin "K2") (pinfunction "C_K2") (pintype "passive"))
      (node (ref "ROT6") (pin "K3") (pinfunction "C_K3") (pintype "passive"))
      (node (ref "ROT6") (pin "K4") (pinfunction "C_K4") (pintype "passive"))
      (node (ref "ROT6") (pin "K5") (pinfunction "C_K5") (pintype "passive"))
      (node (ref "ROT6") (pin "K6") (pinfunction "C_K6") (pintype "passive"))
      (node (ref "ROT6") (pin "K7") (pinfunction "C_K7") (pintype "passive"))
      (node (ref "ROT6") (pin "K8") (pinfunction "C_K8") (pintype "passive"))
      (node (ref "ROT6") (pin "K9") (pinfunction "C_K9") (pintype "passive"))
    )
    (net (code "52") (name "Net-(DO_IC7B-4C)") (class "Default")
      (node (ref "DO_IC7B") (pin "15") (pinfunction "4C_15") (pintype "open_collector"))
      (node (ref "ROT5") (pin "K1") (pinfunction "C_K1") (pintype "passive"))
      (node (ref "ROT5") (pin "K10") (pinfunction "C_K10") (pintype "passive"))
      (node (ref "ROT5") (pin "K12") (pinfunction "C_K12") (pintype "passive"))
      (node (ref "ROT5") (pin "K2") (pinfunction "C_K2") (pintype "passive"))
      (node (ref "ROT5") (pin "K3") (pinfunction "C_K3") (pintype "passive"))
      (node (ref "ROT5") (pin "K4") (pinfunction "C_K4") (pintype "passive"))
      (node (ref "ROT5") (pin "K5") (pinfunction "C_K5") (pintype "passive"))
      (node (ref "ROT5") (pin "K6") (pinfunction "C_K6") (pintype "passive"))
      (node (ref "ROT5") (pin "K7") (pinfunction "C_K7") (pintype "passive"))
      (node (ref "ROT5") (pin "K8") (pinfunction "C_K8") (pintype "passive"))
      (node (ref "ROT5") (pin "K9") (pinfunction "C_K9") (pintype "passive"))
    )
    (net (code "53") (name "Net-(DO_IC7B-5C)") (class "Default")
      (node (ref "DO_IC7B") (pin "14") (pinfunction "5C_14") (pintype "open_collector"))
      (node (ref "ROT4") (pin "K1") (pinfunction "C_K1") (pintype "passive"))
      (node (ref "ROT4") (pin "K10") (pinfunction "C_K10") (pintype "passive"))
      (node (ref "ROT4") (pin "K12") (pinfunction "C_K12") (pintype "passive"))
      (node (ref "ROT4") (pin "K2") (pinfunction "C_K2") (pintype "passive"))
      (node (ref "ROT4") (pin "K3") (pinfunction "C_K3") (pintype "passive"))
      (node (ref "ROT4") (pin "K4") (pinfunction "C_K4") (pintype "passive"))
      (node (ref "ROT4") (pin "K5") (pinfunction "C_K5") (pintype "passive"))
      (node (ref "ROT4") (pin "K6") (pinfunction "C_K6") (pintype "passive"))
      (node (ref "ROT4") (pin "K7") (pinfunction "C_K7") (pintype "passive"))
      (node (ref "ROT4") (pin "K8") (pinfunction "C_K8") (pintype "passive"))
      (node (ref "ROT4") (pin "K9") (pinfunction "C_K9") (pintype "passive"))
    )
    (net (code "54") (name "Net-(DO_IC7B-6C)") (class "Default")
      (node (ref "DO_IC7B") (pin "13") (pinfunction "6C_13") (pintype "open_collector"))
      (node (ref "ROT3") (pin "K1") (pinfunction "C_K1") (pintype "passive"))
      (node (ref "ROT3") (pin "K10") (pinfunction "C_K10") (pintype "passive"))
      (node (ref "ROT3") (pin "K12") (pinfunction "C_K12") (pintype "passive"))
      (node (ref "ROT3") (pin "K2") (pinfunction "C_K2") (pintype "passive"))
      (node (ref "ROT3") (pin "K3") (pinfunction "C_K3") (pintype "passive"))
      (node (ref "ROT3") (pin "K4") (pinfunction "C_K4") (pintype "passive"))
      (node (ref "ROT3") (pin "K5") (pinfunction "C_K5") (pintype "passive"))
      (node (ref "ROT3") (pin "K6") (pinfunction "C_K6") (pintype "passive"))
      (node (ref "ROT3") (pin "K7") (pinfunction "C_K7") (pintype "passive"))
      (node (ref "ROT3") (pin "K8") (pinfunction "C_K8") (pintype "passive"))
      (node (ref "ROT3") (pin "K9") (pinfunction "C_K9") (pintype "passive"))
    )
    (net (code "55") (name "Net-(DO_IC7B-7C)") (class "Default")
      (node (ref "DO_IC7B") (pin "12") (pinfunction "7C_12") (pintype "open_collector"))
      (node (ref "ROT2") (pin "K1") (pinfunction "C_K1") (pintype "passive"))
      (node (ref "ROT2") (pin "K10") (pinfunction "C_K10") (pintype "passive"))
      (node (ref "ROT2") (pin "K12") (pinfunction "C_K12") (pintype "passive"))
      (node (ref "ROT2") (pin "K2") (pinfunction "C_K2") (pintype "passive"))
      (node (ref "ROT2") (pin "K3") (pinfunction "C_K3") (pintype "passive"))
      (node (ref "ROT2") (pin "K4") (pinfunction "C_K4") (pintype "passive"))
      (node (ref "ROT2") (pin "K5") (pinfunction "C_K5") (pintype "passive"))
      (node (ref "ROT2") (pin "K6") (pinfunction "C_K6") (pintype "passive"))
      (node (ref "ROT2") (pin "K7") (pinfunction "C_K7") (pintype "passive"))
      (node (ref "ROT2") (pin "K8") (pinfunction "C_K8") (pintype "passive"))
      (node (ref "ROT2") (pin "K9") (pinfunction "C_K9") (pintype "passive"))
    )
    (net (code "56") (name "Net-(DO_IC7B-8C)") (class "Default")
      (node (ref "DO_IC7B") (pin "11") (pinfunction "8C_11") (pintype "open_collector"))
      (node (ref "ROT1") (pin "K1") (pinfunction "C_K1") (pintype "passive"))
      (node (ref "ROT1") (pin "K10") (pinfunction "C_K10") (pintype "passive"))
      (node (ref "ROT1") (pin "K12") (pinfunction "C_K12") (pintype "passive"))
      (node (ref "ROT1") (pin "K2") (pinfunction "C_K2") (pintype "passive"))
      (node (ref "ROT1") (pin "K3") (pinfunction "C_K3") (pintype "passive"))
      (node (ref "ROT1") (pin "K4") (pinfunction "C_K4") (pintype "passive"))
      (node (ref "ROT1") (pin "K5") (pinfunction "C_K5") (pintype "passive"))
      (node (ref "ROT1") (pin "K6") (pinfunction "C_K6") (pintype "passive"))
      (node (ref "ROT1") (pin "K7") (pinfunction "C_K7") (pintype "passive"))
      (node (ref "ROT1") (pin "K8") (pinfunction "C_K8") (pintype "passive"))
      (node (ref "ROT1") (pin "K9") (pinfunction "C_K9") (pintype "passive"))
    )
    (net (code "57") (name "Net-(DO_IC8-QA)") (class "Default")
      (node (ref "DO_IC8") (pin "15") (pinfunction "QA_15") (pintype "tri_state"))
      (node (ref "MX_R10") (pin "1") (pinfunction "P$1_1") (pintype "passive"))
    )
    (net (code "58") (name "Net-(DO_IC8-QB)") (class "Default")
      (node (ref "DO_IC8") (pin "1") (pinfunction "QB_1") (pintype "tri_state"))
      (node (ref "MX_R10") (pin "2") (pinfunction "P$2_2") (pintype "passive"))
    )
    (net (code "59") (name "Net-(DO_IC8-QC)") (class "Default")
      (node (ref "DO_IC8") (pin "2") (pinfunction "QC_2") (pintype "tri_state"))
      (node (ref "MX_R10") (pin "3") (pinfunction "P$3_3") (pintype "passive"))
    )
    (net (code "60") (name "Net-(DO_IC8-QD)") (class "Default")
      (node (ref "DO_IC8") (pin "3") (pinfunction "QD_3") (pintype "tri_state"))
      (node (ref "MX_R10") (pin "4") (pinfunction "P$4_4") (pintype "passive"))
    )
    (net (code "61") (name "Net-(DO_IC8-QE)") (class "Default")
      (node (ref "DO_IC8") (pin "4") (pinfunction "QE_4") (pintype "tri_state"))
      (node (ref "MX_R10") (pin "5") (pinfunction "P$5_5") (pintype "passive"))
    )
    (net (code "62") (name "Net-(DO_IC8-QF)") (class "Default")
      (node (ref "DO_IC8") (pin "5") (pinfunction "QF_5") (pintype "tri_state"))
      (node (ref "MX_R10") (pin "6") (pinfunction "P$6_6") (pintype "passive"))
    )
    (net (code "63") (name "Net-(DO_IC8-QG)") (class "Default")
      (node (ref "DO_IC8") (pin "6") (pinfunction "QG_6") (pintype "tri_state"))
      (node (ref "MX_R10") (pin "7") (pinfunction "P$7_7") (pintype "passive"))
    )
    (net (code "64") (name "Net-(DO_IC8-QH)") (class "Default")
      (node (ref "DO_IC8") (pin "7") (pinfunction "QH_7") (pintype "tri_state"))
      (node (ref "MX_R10") (pin "8") (pinfunction "P$8_8") (pintype "passive"))
    )
    (net (code "65") (name "Net-(DO_IC8-QH*)") (class "Default")
      (node (ref "DO_IC8") (pin "9") (pinfunction "QH*_9") (pintype "tri_state"))
      (node (ref "DO_IC9") (pin "14") (pinfunction "SER_14") (pintype "input"))
    )
    (net (code "66") (name "Net-(DO_IC9-QF)") (class "Default")
      (node (ref "DO_IC9") (pin "5") (pinfunction "QF_5") (pintype "tri_state"))
      (node (ref "R13") (pin "2") (pinfunction "2_2") (pintype "passive"))
    )
    (net (code "67") (name "Net-(DO_IC9-QG)") (class "Default")
      (node (ref "DO_IC9") (pin "6") (pinfunction "QG_6") (pintype "tri_state"))
      (node (ref "R12") (pin "2") (pinfunction "2_2") (pintype "passive"))
    )
    (net (code "68") (name "Net-(DO_IC9-QH)") (class "Default")
      (node (ref "DO_IC9") (pin "7") (pinfunction "QH_7") (pintype "tri_state"))
      (node (ref "R11") (pin "2") (pinfunction "2_2") (pintype "passive"))
    )
    (net (code "69") (name "Net-(MX_R10-P$9)") (class "Default")
      (node (ref "MX_R10") (pin "9") (pinfunction "P$9_9") (pintype "passive"))
      (node (ref "ROT1") (pin "A1") (pinfunction "A_A1") (pintype "passive"))
      (node (ref "ROT2") (pin "A1") (pinfunction "A_A1") (pintype "passive"))
      (node (ref "ROT3") (pin "A1") (pinfunction "A_A1") (pintype "passive"))
      (node (ref "ROT4") (pin "A1") (pinfunction "A_A1") (pintype "passive"))
      (node (ref "ROT5") (pin "A1") (pinfunction "A_A1") (pintype "passive"))
      (node (ref "ROT6") (pin "A1") (pinfunction "A_A1") (pintype "passive"))
      (node (ref "ROT7") (pin "A1") (pinfunction "A_A1") (pintype "passive"))
      (node (ref "ROT8") (pin "A1") (pinfunction "A_A1") (pintype "passive"))
    )
    (net (code "70") (name "Net-(MX_R10-P$10)") (class "Default")
      (node (ref "MX_R10") (pin "10") (pinfunction "P$10_10") (pintype "passive"))
      (node (ref "ROT1") (pin "A2") (pinfunction "A_A2") (pintype "passive"))
      (node (ref "ROT2") (pin "A2") (pinfunction "A_A2") (pintype "passive"))
      (node (ref "ROT3") (pin "A2") (pinfunction "A_A2") (pintype "passive"))
      (node (ref "ROT4") (pin "A2") (pinfunction "A_A2") (pintype "passive"))
      (node (ref "ROT5") (pin "A2") (pinfunction "A_A2") (pintype "passive"))
      (node (ref "ROT6") (pin "A2") (pinfunction "A_A2") (pintype "passive"))
      (node (ref "ROT7") (pin "A2") (pinfunction "A_A2") (pintype "passive"))
      (node (ref "ROT8") (pin "A2") (pinfunction "A_A2") (pintype "passive"))
    )
    (net (code "71") (name "Net-(MX_R10-P$11)") (class "Default")
      (node (ref "MX_R10") (pin "11") (pinfunction "P$11_11") (pintype "passive"))
      (node (ref "ROT1") (pin "A3") (pinfunction "A_A3") (pintype "passive"))
      (node (ref "ROT2") (pin "A3") (pinfunction "A_A3") (pintype "passive"))
      (node (ref "ROT3") (pin "A3") (pinfunction "A_A3") (pintype "passive"))
      (node (ref "ROT4") (pin "A3") (pinfunction "A_A3") (pintype "passive"))
      (node (ref "ROT5") (pin "A3") (pinfunction "A_A3") (pintype "passive"))
      (node (ref "ROT6") (pin "A3") (pinfunction "A_A3") (pintype "passive"))
      (node (ref "ROT7") (pin "A3") (pinfunction "A_A3") (pintype "passive"))
      (node (ref "ROT8") (pin "A3") (pinfunction "A_A3") (pintype "passive"))
    )
    (net (code "72") (name "Net-(MX_R10-P$12)") (class "Default")
      (node (ref "MX_R10") (pin "12") (pinfunction "P$12_12") (pintype "passive"))
      (node (ref "ROT1") (pin "A4") (pinfunction "A_A4") (pintype "passive"))
      (node (ref "ROT2") (pin "A4") (pinfunction "A_A4") (pintype "passive"))
      (node (ref "ROT3") (pin "A4") (pinfunction "A_A4") (pintype "passive"))
      (node (ref "ROT4") (pin "A4") (pinfunction "A_A4") (pintype "passive"))
      (node (ref "ROT5") (pin "A4") (pinfunction "A_A4") (pintype "passive"))
      (node (ref "ROT6") (pin "A4") (pinfunction "A_A4") (pintype "passive"))
      (node (ref "ROT7") (pin "A4") (pinfunction "A_A4") (pintype "passive"))
      (node (ref "ROT8") (pin "A4") (pinfunction "A_A4") (pintype "passive"))
    )
    (net (code "73") (name "Net-(MX_R10-P$13)") (class "Default")
      (node (ref "MX_R10") (pin "13") (pinfunction "P$13_13") (pintype "passive"))
      (node (ref "ROT1") (pin "A5") (pinfunction "A_A5") (pintype "passive"))
      (node (ref "ROT2") (pin "A5") (pinfunction "A_A5") (pintype "passive"))
      (node (ref "ROT3") (pin "A5") (pinfunction "A_A5") (pintype "passive"))
      (node (ref "ROT4") (pin "A5") (pinfunction "A_A5") (pintype "passive"))
      (node (ref "ROT5") (pin "A5") (pinfunction "A_A5") (pintype "passive"))
      (node (ref "ROT6") (pin "A5") (pinfunction "A_A5") (pintype "passive"))
      (node (ref "ROT7") (pin "A5") (pinfunction "A_A5") (pintype "passive"))
      (node (ref "ROT8") (pin "A5") (pinfunction "A_A5") (pintype "passive"))
    )
    (net (code "74") (name "Net-(MX_R10-P$14)") (class "Default")
      (node (ref "MX_R10") (pin "14") (pinfunction "P$14_14") (pintype "passive"))
      (node (ref "ROT1") (pin "A6") (pinfunction "A_A6") (pintype "passive"))
      (node (ref "ROT2") (pin "A6") (pinfunction "A_A6") (pintype "passive"))
      (node (ref "ROT3") (pin "A6") (pinfunction "A_A6") (pintype "passive"))
      (node (ref "ROT4") (pin "A6") (pinfunction "A_A6") (pintype "passive"))
      (node (ref "ROT5") (pin "A6") (pinfunction "A_A6") (pintype "passive"))
      (node (ref "ROT6") (pin "A6") (pinfunction "A_A6") (pintype "passive"))
      (node (ref "ROT7") (pin "A6") (pinfunction "A_A6") (pintype "passive"))
      (node (ref "ROT8") (pin "A6") (pinfunction "A_A6") (pintype "passive"))
    )
    (net (code "75") (name "Net-(MX_R10-P$15)") (class "Default")
      (node (ref "MX_R10") (pin "15") (pinfunction "P$15_15") (pintype "passive"))
      (node (ref "ROT1") (pin "A7") (pinfunction "A_A7") (pintype "passive"))
      (node (ref "ROT2") (pin "A7") (pinfunction "A_A7") (pintype "passive"))
      (node (ref "ROT3") (pin "A7") (pinfunction "A_A7") (pintype "passive"))
      (node (ref "ROT4") (pin "A7") (pinfunction "A_A7") (pintype "passive"))
      (node (ref "ROT5") (pin "A7") (pinfunction "A_A7") (pintype "passive"))
      (node (ref "ROT6") (pin "A7") (pinfunction "A_A7") (pintype "passive"))
      (node (ref "ROT7") (pin "A7") (pinfunction "A_A7") (pintype "passive"))
      (node (ref "ROT8") (pin "A7") (pinfunction "A_A7") (pintype "passive"))
    )
    (net (code "76") (name "Net-(MX_R10-P$16)") (class "Default")
      (node (ref "MX_R10") (pin "16") (pinfunction "P$16_16") (pintype "passive"))
      (node (ref "ROT1") (pin "A8") (pinfunction "A_A8") (pintype "passive"))
      (node (ref "ROT2") (pin "A8") (pinfunction "A_A8") (pintype "passive"))
      (node (ref "ROT3") (pin "A8") (pinfunction "A_A8") (pintype "passive"))
      (node (ref "ROT4") (pin "A8") (pinfunction "A_A8") (pintype "passive"))
      (node (ref "ROT5") (pin "A8") (pinfunction "A_A8") (pintype "passive"))
      (node (ref "ROT6") (pin "A8") (pinfunction "A_A8") (pintype "passive"))
      (node (ref "ROT7") (pin "A8") (pinfunction "A_A8") (pintype "passive"))
      (node (ref "ROT8") (pin "A8") (pinfunction "A_A8") (pintype "passive"))
    )
    (net (code "77") (name "Net-(ROT1C-A)") (class "Default")
      (node (ref "R12") (pin "1") (pinfunction "1_1") (pintype "passive"))
      (node (ref "ROT1") (pin "A10") (pinfunction "A_A10") (pintype "passive"))
      (node (ref "ROT2") (pin "A10") (pinfunction "A_A10") (pintype "passive"))
      (node (ref "ROT3") (pin "A10") (pinfunction "A_A10") (pintype "passive"))
      (node (ref "ROT4") (pin "A10") (pinfunction "A_A10") (pintype "passive"))
      (node (ref "ROT5") (pin "A10") (pinfunction "A_A10") (pintype "passive"))
      (node (ref "ROT6") (pin "A10") (pinfunction "A_A10") (pintype "passive"))
      (node (ref "ROT7") (pin "A10") (pinfunction "A_A10") (pintype "passive"))
      (node (ref "ROT8") (pin "A10") (pinfunction "A_A10") (pintype "passive"))
    )
    (net (code "78") (name "Net-(ROT1D-A)") (class "Default")
      (node (ref "R13") (pin "1") (pinfunction "1_1") (pintype "passive"))
      (node (ref "ROT1") (pin "A12") (pinfunction "A_A12") (pintype "passive"))
      (node (ref "ROT2") (pin "A12") (pinfunction "A_A12") (pintype "passive"))
      (node (ref "ROT3") (pin "A12") (pinfunction "A_A12") (pintype "passive"))
      (node (ref "ROT4") (pin "A12") (pinfunction "A_A12") (pintype "passive"))
      (node (ref "ROT5") (pin "A12") (pinfunction "A_A12") (pintype "passive"))
      (node (ref "ROT6") (pin "A12") (pinfunction "A_A12") (pintype "passive"))
      (node (ref "ROT7") (pin "A12") (pinfunction "A_A12") (pintype "passive"))
      (node (ref "ROT8") (pin "A12") (pinfunction "A_A12") (pintype "passive"))
    )
    (net (code "79") (name "Net-(ROT1L-A)") (class "Default")
      (node (ref "R11") (pin "1") (pinfunction "1_1") (pintype "passive"))
      (node (ref "ROT1") (pin "A9") (pinfunction "A_A9") (pintype "passive"))
      (node (ref "ROT2") (pin "A9") (pinfunction "A_A9") (pintype "passive"))
      (node (ref "ROT3") (pin "A9") (pinfunction "A_A9") (pintype "passive"))
      (node (ref "ROT4") (pin "A9") (pinfunction "A_A9") (pintype "passive"))
      (node (ref "ROT5") (pin "A9") (pinfunction "A_A9") (pintype "passive"))
      (node (ref "ROT6") (pin "A9") (pinfunction "A_A9") (pintype "passive"))
      (node (ref "ROT7") (pin "A9") (pinfunction "A_A9") (pintype "passive"))
      (node (ref "ROT8") (pin "A9") (pinfunction "A_A9") (pintype "passive"))
    )
    (net (code "80") (name "R1B") (class "Default")
      (node (ref "DO_R7") (pin "16") (pinfunction "P$16_16") (pintype "passive"))
      (node (ref "ROT1") (pin "LED_BLUE") (pinfunction "LED_BLUE_LED_BLUE") (pintype "bidirectional"))
    )
    (net (code "81") (name "R1G") (class "Default")
      (node (ref "DO_R6") (pin "8") (pinfunction "P$8_8") (pintype "passive"))
      (node (ref "ROT1") (pin "LED_GREEN") (pinfunction "LED_GREEN_LED_GREEN") (pintype "bidirectional"))
    )
    (net (code "82") (name "R1R") (class "Default")
      (node (ref "DO_R5") (pin "8") (pinfunction "P$8_8") (pintype "passive"))
      (node (ref "ROT1") (pin "LED_RED") (pinfunction "LED_RED_LED_RED") (pintype "bidirectional"))
    )
    (net (code "83") (name "R2B") (class "Default")
      (node (ref "DO_R7") (pin "15") (pinfunction "P$15_15") (pintype "passive"))
      (node (ref "ROT2") (pin "LED_BLUE") (pinfunction "LED_BLUE_LED_BLUE") (pintype "bidirectional"))
    )
    (net (code "84") (name "R2G") (class "Default")
      (node (ref "DO_R6") (pin "7") (pinfunction "P$7_7") (pintype "passive"))
      (node (ref "ROT2") (pin "LED_GREEN") (pinfunction "LED_GREEN_LED_GREEN") (pintype "bidirectional"))
    )
    (net (code "85") (name "R2R") (class "Default")
      (node (ref "DO_R5") (pin "7") (pinfunction "P$7_7") (pintype "passive"))
      (node (ref "ROT2") (pin "LED_RED") (pinfunction "LED_RED_LED_RED") (pintype "bidirectional"))
    )
    (net (code "86") (name "R3B") (class "Default")
      (node (ref "DO_R7") (pin "14") (pinfunction "P$14_14") (pintype "passive"))
      (node (ref "ROT3") (pin "LED_BLUE") (pinfunction "LED_BLUE_LED_BLUE") (pintype "bidirectional"))
    )
    (net (code "87") (name "R3G") (class "Default")
      (node (ref "DO_R6") (pin "6") (pinfunction "P$6_6") (pintype "passive"))
      (node (ref "ROT3") (pin "LED_GREEN") (pinfunction "LED_GREEN_LED_GREEN") (pintype "bidirectional"))
    )
    (net (code "88") (name "R3R") (class "Default")
      (node (ref "DO_R5") (pin "6") (pinfunction "P$6_6") (pintype "passive"))
      (node (ref "ROT3") (pin "LED_RED") (pinfunction "LED_RED_LED_RED") (pintype "bidirectional"))
    )
    (net (code "89") (name "R4B") (class "Default")
      (node (ref "DO_R7") (pin "13") (pinfunction "P$13_13") (pintype "passive"))
      (node (ref "ROT4") (pin "LED_BLUE") (pinfunction "LED_BLUE_LED_BLUE") (pintype "bidirectional"))
    )
    (net (code "90") (name "R4G") (class "Default")
      (node (ref "DO_R6") (pin "5") (pinfunction "P$5_5") (pintype "passive"))
      (node (ref "ROT4") (pin "LED_GREEN") (pinfunction "LED_GREEN_LED_GREEN") (pintype "bidirectional"))
    )
    (net (code "91") (name "R4R") (class "Default")
      (node (ref "DO_R5") (pin "5") (pinfunction "P$5_5") (pintype "passive"))
      (node (ref "ROT4") (pin "LED_RED") (pinfunction "LED_RED_LED_RED") (pintype "bidirectional"))
    )
    (net (code "92") (name "R5B") (class "Default")
      (node (ref "DO_R7") (pin "12") (pinfunction "P$12_12") (pintype "passive"))
      (node (ref "ROT5") (pin "LED_BLUE") (pinfunction "LED_BLUE_LED_BLUE") (pintype "bidirectional"))
    )
    (net (code "93") (name "R5G") (class "Default")
      (node (ref "DO_R6") (pin "4") (pinfunction "P$4_4") (pintype "passive"))
      (node (ref "ROT5") (pin "LED_GREEN") (pinfunction "LED_GREEN_LED_GREEN") (pintype "bidirectional"))
    )
    (net (code "94") (name "R5R") (class "Default")
      (node (ref "DO_R5") (pin "4") (pinfunction "P$4_4") (pintype "passive"))
      (node (ref "ROT5") (pin "LED_RED") (pinfunction "LED_RED_LED_RED") (pintype "bidirectional"))
    )
    (net (code "95") (name "R6B") (class "Default")
      (node (ref "DO_R7") (pin "11") (pinfunction "P$11_11") (pintype "passive"))
      (node (ref "ROT6") (pin "LED_BLUE") (pinfunction "LED_BLUE_LED_BLUE") (pintype "bidirectional"))
    )
    (net (code "96") (name "R6G") (class "Default")
      (node (ref "DO_R6") (pin "3") (pinfunction "P$3_3") (pintype "passive"))
      (node (ref "ROT6") (pin "LED_GREEN") (pinfunction "LED_GREEN_LED_GREEN") (pintype "bidirectional"))
    )
    (net (code "97") (name "R6R") (class "Default")
      (node (ref "DO_R5") (pin "3") (pinfunction "P$3_3") (pintype "passive"))
      (node (ref "ROT6") (pin "LED_RED") (pinfunction "LED_RED_LED_RED") (pintype "bidirectional"))
    )
    (net (code "98") (name "R7B") (class "Default")
      (node (ref "DO_R7") (pin "10") (pinfunction "P$10_10") (pintype "passive"))
      (node (ref "ROT7") (pin "LED_BLUE") (pinfunction "LED_BLUE_LED_BLUE") (pintype "bidirectional"))
    )
    (net (code "99") (name "R7G") (class "Default")
      (node (ref "DO_R6") (pin "2") (pinfunction "P$2_2") (pintype "passive"))
      (node (ref "ROT7") (pin "LED_GREEN") (pinfunction "LED_GREEN_LED_GREEN") (pintype "bidirectional"))
    )
    (net (code "100") (name "R7R") (class "Default")
      (node (ref "DO_R5") (pin "2") (pinfunction "P$2_2") (pintype "passive"))
      (node (ref "ROT7") (pin "LED_RED") (pinfunction "LED_RED_LED_RED") (pintype "bidirectional"))
    )
    (net (code "101") (name "R8B") (class "Default")
      (node (ref "DO_R7") (pin "9") (pinfunction "P$9_9") (pintype "passive"))
      (node (ref "ROT8") (pin "LED_BLUE") (pinfunction "LED_BLUE_LED_BLUE") (pintype "bidirectional"))
    )
    (net (code "102") (name "R8G") (class "Default")
      (node (ref "DO_R6") (pin "1") (pinfunction "P$1_1") (pintype "passive"))
      (node (ref "ROT8") (pin "LED_GREEN") (pinfunction "LED_GREEN_LED_GREEN") (pintype "bidirectional"))
    )
    (net (code "103") (name "R8R") (class "Default")
      (node (ref "DO_R5") (pin "1") (pinfunction "P$1_1") (pintype "passive"))
      (node (ref "ROT8") (pin "LED_RED") (pinfunction "LED_RED_LED_RED") (pintype "bidirectional"))
    )
    (net (code "104") (name "RC-I") (class "Default")
      (node (ref "DI_IC1") (pin "1") (pinfunction "SH/~{LD}_1") (pintype "input"))
      (node (ref "DI_IC2") (pin "1") (pinfunction "SH/~{LD}_1") (pintype "input"))
      (node (ref "DI_IC3") (pin "1") (pinfunction "SH/~{LD}_1") (pintype "input"))
      (node (ref "J1") (pin "9") (pinfunction "9_9") (pintype "passive"))
      (node (ref "J2") (pin "9") (pinfunction "9_9") (pintype "passive"))
    )
    (net (code "105") (name "RC-O") (class "Default")
      (node (ref "DO_IC4_R") (pin "12") (pinfunction "RCK_12") (pintype "input"))
      (node (ref "DO_IC5_G") (pin "12") (pinfunction "RCK_12") (pintype "input"))
      (node (ref "DO_IC6_B") (pin "12") (pinfunction "RCK_12") (pintype "input"))
      (node (ref "DO_IC7") (pin "12") (pinfunction "RCK_12") (pintype "input"))
      (node (ref "DO_IC8") (pin "12") (pinfunction "RCK_12") (pintype "input"))
      (node (ref "DO_IC9") (pin "12") (pinfunction "RCK_12") (pintype "input"))
      (node (ref "J1") (pin "10") (pinfunction "10_10") (pintype "passive"))
      (node (ref "J2") (pin "10") (pinfunction "10_10") (pintype "passive"))
    )
    (net (code "106") (name "ROT1A") (class "Default")
      (node (ref "DI_IC1") (pin "12") (pinfunction "I2_12") (pintype "input"))
      (node (ref "DI_R2") (pin "4") (pinfunction "4_4") (pintype "passive"))
      (node (ref "ROT1") (pin "A") (pinfunction "A_A") (pintype "bidirectional"))
    )
    (net (code "107") (name "ROT1B") (class "Default")
      (node (ref "DI_IC1") (pin "11") (pinfunction "I1_11") (pintype "input"))
      (node (ref "DI_R2") (pin "5") (pinfunction "5_5") (pintype "passive"))
      (node (ref "ROT1") (pin "B") (pinfunction "B_B") (pintype "bidirectional"))
    )
    (net (code "108") (name "ROT2A") (class "Default")
      (node (ref "DI_IC1") (pin "14") (pinfunction "I4_14") (pintype "input"))
      (node (ref "DI_R2") (pin "2") (pinfunction "2_2") (pintype "passive"))
      (node (ref "ROT2") (pin "A") (pinfunction "A_A") (pintype "bidirectional"))
    )
    (net (code "109") (name "ROT2B") (class "Default")
      (node (ref "DI_IC1") (pin "13") (pinfunction "I3_13") (pintype "input"))
      (node (ref "DI_R2") (pin "3") (pinfunction "3_3") (pintype "passive"))
      (node (ref "ROT2") (pin "B") (pinfunction "B_B") (pintype "bidirectional"))
    )
    (net (code "110") (name "ROT3A") (class "Default")
      (node (ref "DI_IC1") (pin "4") (pinfunction "I6_4") (pintype "input"))
      (node (ref "DI_R1") (pin "3") (pinfunction "3_3") (pintype "passive"))
      (node (ref "ROT3") (pin "A") (pinfunction "A_A") (pintype "bidirectional"))
    )
    (net (code "111") (name "ROT3B") (class "Default")
      (node (ref "DI_IC1") (pin "3") (pinfunction "I5_3") (pintype "input"))
      (node (ref "DI_R1") (pin "2") (pinfunction "2_2") (pintype "passive"))
      (node (ref "ROT3") (pin "B") (pinfunction "B_B") (pintype "bidirectional"))
    )
    (net (code "112") (name "ROT4A") (class "Default")
      (node (ref "DI_IC1") (pin "6") (pinfunction "I8_6") (pintype "input"))
      (node (ref "DI_R1") (pin "5") (pinfunction "5_5") (pintype "passive"))
      (node (ref "ROT4") (pin "A") (pinfunction "A_A") (pintype "bidirectional"))
    )
    (net (code "113") (name "ROT4B") (class "Default")
      (node (ref "DI_IC1") (pin "5") (pinfunction "I7_5") (pintype "input"))
      (node (ref "DI_R1") (pin "4") (pinfunction "4_4") (pintype "passive"))
      (node (ref "ROT4") (pin "B") (pinfunction "B_B") (pintype "bidirectional"))
    )
    (net (code "114") (name "ROT5A") (class "Default")
      (node (ref "DI_IC2") (pin "12") (pinfunction "I2_12") (pintype "input"))
      (node (ref "DI_R4") (pin "4") (pinfunction "4_4") (pintype "passive"))
      (node (ref "ROT5") (pin "A") (pinfunction "A_A") (pintype "bidirectional"))
    )
    (net (code "115") (name "ROT5B") (class "Default")
      (node (ref "DI_IC2") (pin "11") (pinfunction "I1_11") (pintype "input"))
      (node (ref "DI_R4") (pin "5") (pinfunction "5_5") (pintype "passive"))
      (node (ref "ROT5") (pin "B") (pinfunction "B_B") (pintype "bidirectional"))
    )
    (net (code "116") (name "ROT6A") (class "Default")
      (node (ref "DI_IC2") (pin "14") (pinfunction "I4_14") (pintype "input"))
      (node (ref "DI_R4") (pin "2") (pinfunction "2_2") (pintype "passive"))
      (node (ref "ROT6") (pin "A") (pinfunction "A_A") (pintype "bidirectional"))
    )
    (net (code "117") (name "ROT6B") (class "Default")
      (node (ref "DI_IC2") (pin "13") (pinfunction "I3_13") (pintype "input"))
      (node (ref "DI_R4") (pin "3") (pinfunction "3_3") (pintype "passive"))
      (node (ref "ROT6") (pin "B") (pinfunction "B_B") (pintype "bidirectional"))
    )
    (net (code "118") (name "ROT7A") (class "Default")
      (node (ref "DI_IC2") (pin "4") (pinfunction "I6_4") (pintype "input"))
      (node (ref "DI_R3") (pin "3") (pinfunction "3_3") (pintype "passive"))
      (node (ref "ROT7") (pin "A") (pinfunction "A_A") (pintype "bidirectional"))
    )
    (net (code "119") (name "ROT7B") (class "Default")
      (node (ref "DI_IC2") (pin "3") (pinfunction "I5_3") (pintype "input"))
      (node (ref "DI_R3") (pin "2") (pinfunction "2_2") (pintype "passive"))
      (node (ref "ROT7") (pin "B") (pinfunction "B_B") (pintype "bidirectional"))
    )
    (net (code "120") (name "ROT8A") (class "Default")
      (node (ref "DI_IC2") (pin "6") (pinfunction "I8_6") (pintype "input"))
      (node (ref "DI_R3") (pin "5") (pinfunction "5_5") (pintype "passive"))
      (node (ref "ROT8") (pin "A") (pinfunction "A_A") (pintype "bidirectional"))
    )
    (net (code "121") (name "ROT8B") (class "Default")
      (node (ref "DI_IC2") (pin "5") (pinfunction "I7_5") (pintype "input"))
      (node (ref "DI_R3") (pin "4") (pinfunction "4_4") (pintype "passive"))
      (node (ref "ROT8") (pin "B") (pinfunction "B_B") (pintype "bidirectional"))
    )
    (net (code "122") (name "SC") (class "Default")
      (node (ref "DI_IC1") (pin "2") (pinfunction "CLK_2") (pintype "input"))
      (node (ref "DI_IC2") (pin "2") (pinfunction "CLK_2") (pintype "input"))
      (node (ref "DI_IC3") (pin "2") (pinfunction "CLK_2") (pintype "input"))
      (node (ref "DO_IC4_R") (pin "13") (pinfunction "SCK_13") (pintype "input"))
      (node (ref "DO_IC5_G") (pin "13") (pinfunction "SCK_13") (pintype "input"))
      (node (ref "DO_IC6_B") (pin "13") (pinfunction "SCK_13") (pintype "input"))
      (node (ref "DO_IC7") (pin "11") (pinfunction "SCK_11") (pintype "input"))
      (node (ref "DO_IC8") (pin "11") (pinfunction "SCK_11") (pintype "input"))
      (node (ref "DO_IC9") (pin "11") (pinfunction "SCK_11") (pintype "input"))
      (node (ref "J1") (pin "7") (pinfunction "7_7") (pintype "passive"))
      (node (ref "J1") (pin "8") (pinfunction "8_8") (pintype "passive"))
      (node (ref "J2") (pin "7") (pinfunction "7_7") (pintype "passive"))
      (node (ref "J2") (pin "8") (pinfunction "8_8") (pintype "passive"))
    )
    (net (code "123") (name "SI-INPUT") (class "Default")
      (node (ref "DI_IC3") (pin "10") (pinfunction "SER_10") (pintype "input"))
      (node (ref "DI_R6") (pin "6") (pinfunction "6_6") (pintype "passive"))
      (node (ref "J2") (pin "5") (pinfunction "5_5") (pintype "passive"))
    )
    (net (code "124") (name "SI-OUTPUT") (class "Default")
      (node (ref "DI_IC1") (pin "9") (pinfunction "QH_9") (pintype "output"))
      (node (ref "J1") (pin "5") (pinfunction "5_5") (pintype "passive"))
    )
    (net (code "125") (name "SO-INPUT") (class "Default")
      (node (ref "DO_IC4_R") (pin "3") (pinfunction "SER_3") (pintype "input"))
      (node (ref "J1") (pin "6") (pinfunction "6_6") (pintype "passive"))
    )
    (net (code "126") (name "SO-OUTPUT") (class "Default")
      (node (ref "DO_IC9") (pin "9") (pinfunction "QH*_9") (pintype "tri_state"))
      (node (ref "J2") (pin "6") (pinfunction "6_6") (pintype "passive"))
    )
    (net (code "127") (name "SW1") (class "Default")
      (node (ref "DI_IC3B") (pin "8") (pinfunction "8B_8") (pintype "input"))
      (node (ref "ROT1") (pin "SWITCH") (pinfunction "SW_SWITCH") (pintype "bidirectional"))
    )
    (net (code "128") (name "SW2") (class "Default")
      (node (ref "DI_IC3B") (pin "7") (pinfunction "7B_7") (pintype "input"))
      (node (ref "ROT2") (pin "SWITCH") (pinfunction "SW_SWITCH") (pintype "bidirectional"))
    )
    (net (code "129") (name "SW3") (class "Default")
      (node (ref "DI_IC3B") (pin "6") (pinfunction "6B_6") (pintype "input"))
      (node (ref "ROT3") (pin "SWITCH") (pinfunction "SW_SWITCH") (pintype "bidirectional"))
    )
    (net (code "130") (name "SW4") (class "Default")
      (node (ref "DI_IC3B") (pin "5") (pinfunction "5B_5") (pintype "input"))
      (node (ref "ROT4") (pin "SWITCH") (pinfunction "SW_SWITCH") (pintype "bidirectional"))
    )
    (net (code "131") (name "SW5") (class "Default")
      (node (ref "DI_IC3B") (pin "4") (pinfunction "4B_4") (pintype "input"))
      (node (ref "ROT5") (pin "SWITCH") (pinfunction "SW_SWITCH") (pintype "bidirectional"))
    )
    (net (code "132") (name "SW6") (class "Default")
      (node (ref "DI_IC3B") (pin "3") (pinfunction "3B_3") (pintype "input"))
      (node (ref "ROT6") (pin "SWITCH") (pinfunction "SW_SWITCH") (pintype "bidirectional"))
    )
    (net (code "133") (name "SW7") (class "Default")
      (node (ref "DI_IC3B") (pin "2") (pinfunction "2B_2") (pintype "input"))
      (node (ref "ROT7") (pin "SWITCH") (pinfunction "SW_SWITCH") (pintype "bidirectional"))
    )
    (net (code "134") (name "SW8") (class "Default")
      (node (ref "DI_IC3B") (pin "1") (pinfunction "1B_1") (pintype "input"))
      (node (ref "ROT8") (pin "SWITCH") (pinfunction "SW_SWITCH") (pintype "bidirectional"))
    )
    (net (code "135") (name "unconnected-(DI_IC1-~{QH}-Pad7)") (class "Default")
      (node (ref "DI_IC1") (pin "7") (pinfunction "~{QH}_7") (pintype "output"))
    )
    (net (code "136") (name "unconnected-(DI_IC2-~{QH}-Pad7)") (class "Default")
      (node (ref "DI_IC2") (pin "7") (pinfunction "~{QH}_7") (pintype "output"))
    )
    (net (code "137") (name "unconnected-(DI_IC3-~{QH}-Pad7)") (class "Default")
      (node (ref "DI_IC3") (pin "7") (pinfunction "~{QH}_7") (pintype "output"))
    )
    (net (code "138") (name "unconnected-(DI_IC3B-C-Pad10)") (class "Default")
      (node (ref "DI_IC3B") (pin "10") (pinfunction "C_10") (pintype "passive"))
    )
    (net (code "139") (name "unconnected-(DI_R2-Pad6)") (class "Default")
      (node (ref "DI_R2") (pin "6") (pinfunction "6_6") (pintype "passive"))
    )
    (net (code "140") (name "unconnected-(DI_R3-Pad6)") (class "Default")
      (node (ref "DI_R3") (pin "6") (pinfunction "6_6") (pintype "passive"))
    )
    (net (code "141") (name "unconnected-(DI_R5-Pad6)") (class "Default")
      (node (ref "DI_R5") (pin "6") (pinfunction "6_6") (pintype "passive"))
    )
    (net (code "142") (name "unconnected-(DO_IC4_R-NC-Pad20)") (class "Default")
      (node (ref "DO_IC4_R") (pin "20") (pinfunction "NC_20") (pintype "no_connect"))
    )
    (net (code "143") (name "unconnected-(DO_IC4_R-NC1-Pad1)") (class "Default")
      (node (ref "DO_IC4_R") (pin "1") (pinfunction "NC1_1") (pintype "no_connect"))
    )
    (net (code "144") (name "unconnected-(DO_IC5_G-NC-Pad20)") (class "Default")
      (node (ref "DO_IC5_G") (pin "20") (pinfunction "NC_20") (pintype "no_connect"))
    )
    (net (code "145") (name "unconnected-(DO_IC5_G-NC1-Pad1)") (class "Default")
      (node (ref "DO_IC5_G") (pin "1") (pinfunction "NC1_1") (pintype "no_connect"))
    )
    (net (code "146") (name "unconnected-(DO_IC6_B-NC-Pad20)") (class "Default")
      (node (ref "DO_IC6_B") (pin "20") (pinfunction "NC_20") (pintype "no_connect"))
    )
    (net (code "147") (name "unconnected-(DO_IC6_B-NC1-Pad1)") (class "Default")
      (node (ref "DO_IC6_B") (pin "1") (pinfunction "NC1_1") (pintype "no_connect"))
    )
    (net (code "148") (name "unconnected-(DO_IC9-QA-Pad15)") (class "Default")
      (node (ref "DO_IC9") (pin "15") (pinfunction "QA_15") (pintype "tri_state"))
    )
    (net (code "149") (name "unconnected-(DO_IC9-QB-Pad1)") (class "Default")
      (node (ref "DO_IC9") (pin "1") (pinfunction "QB_1") (pintype "tri_state"))
    )
    (net (code "150") (name "unconnected-(DO_IC9-QC-Pad2)") (class "Default")
      (node (ref "DO_IC9") (pin "2") (pinfunction "QC_2") (pintype "tri_state"))
    )
    (net (code "151") (name "unconnected-(DO_IC9-QD-Pad3)") (class "Default")
      (node (ref "DO_IC9") (pin "3") (pinfunction "QD_3") (pintype "tri_state"))
    )
    (net (code "152") (name "unconnected-(DO_IC9-QE-Pad4)") (class "Default")
      (node (ref "DO_IC9") (pin "4") (pinfunction "QE_4") (pintype "tri_state"))
    )
  )
)
